# USB_A_USB_C.net
KiCad netlist of a schematic drawn in Altium Designer
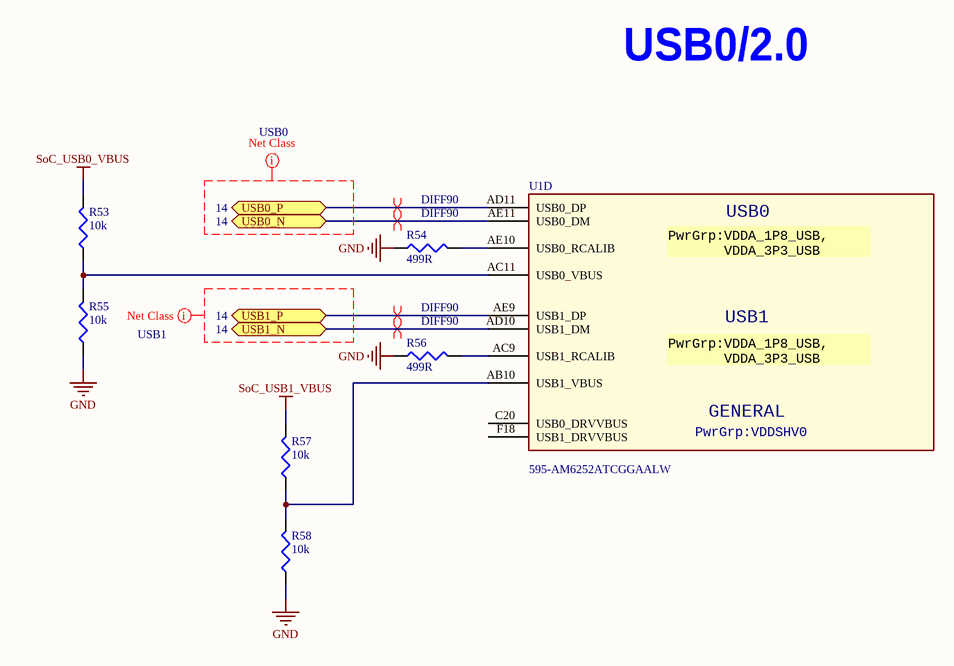
[diagram p0: USB_A & USB_C.SchDoc]

(export (version "E")
  (design (tool "Eeschema 10.0.6"))
  (components
    (comp (ref "R53")
      (value "10k")
      (footprint "R0402")
      (description "RES 10.0K OHM 1/16W 1% 0402 SMD")
      (fields
        (field (name "MANUFACTURER") "Yageo")
        (field (name "MANUFACTURER PART NUMBER") "RC0402FR-0710KL")
      )
      (libsource (lib "Schlib AM625") (part "RC0402FR-0710KL"))
    )
    (comp (ref "R54")
      (value "499R")
      (footprint "R0402")
      (description "RES SMD 499 OHM 0.1% 1/16W 0402")
      (fields
        (field (name "MANUFACTURER") "Yageo")
        (field (name "MANUFACTURER PART NUMBER") "RT0402BRD07499RL")
      )
      (libsource (lib "Schlib AM625") (part "RT0402BRD07499RL"))
    )
    (comp (ref "R55")
      (value "10k")
      (footprint "R0402")
      (description "RES 10.0K OHM 1/16W 1% 0402 SMD")
      (fields
        (field (name "MANUFACTURER") "Yageo")
        (field (name "MANUFACTURER PART NUMBER") "RC0402FR-0710KL")
      )
      (libsource (lib "Schlib AM625") (part "RC0402FR-0710KL"))
    )
    (comp (ref "R56")
      (value "499R")
      (footprint "R0402")
      (description "RES SMD 499 OHM 0.1% 1/16W 0402")
      (fields
        (field (name "MANUFACTURER") "Yageo")
        (field (name "MANUFACTURER PART NUMBER") "RT0402BRD07499RL")
      )
      (libsource (lib "Schlib AM625") (part "RT0402BRD07499RL"))
    )
    (comp (ref "R57")
      (value "10k")
      (footprint "R0402")
      (description "RES 10.0K OHM 1/16W 1% 0402 SMD")
      (fields
        (field (name "MANUFACTURER") "Yageo")
        (field (name "MANUFACTURER PART NUMBER") "RC0402FR-0710KL")
      )
      (libsource (lib "Schlib AM625") (part "RC0402FR-0710KL"))
    )
    (comp (ref "R58")
      (value "10k")
      (footprint "R0402")
      (description "RES 10.0K OHM 1/16W 1% 0402 SMD")
      (fields
        (field (name "MANUFACTURER") "Yageo")
        (field (name "MANUFACTURER PART NUMBER") "RC0402FR-0710KL")
      )
      (libsource (lib "Schlib AM625") (part "RC0402FR-0710KL"))
    )
    (comp (ref "U1")
      (value "AM62-EVM_BGA425")
      (footprint "BGA425C50P25X25_1300X1300X89")
      (description "ARM® Cortex®-A53 Microprocessor IC Sitara™ 2 Core, 64-Bit 1.4GHz 425-FCCSP (13x13)")
      (fields
        (field (name "MANUFACTURER") "Texas Instruments")
        (field (name "MANUFACTURER PART NUMBER") "AM6252ATCGGAALW")
        (field (name "SUPPLIER PART NUMBER 1") "595-AM6252ATCGGAALW")
      )
      (libsource (lib "Schlib AM625") (part "AM62-EVM_BGA425"))
    )
  )
  (nets
    (net (code "1") (name "/USB0_N") (class "Default")
      (node (ref "U1") (pin "AE11") (pinfunction "USB0_DM_AE11") (pintype "passive"))
    )
    (net (code "2") (name "/USB0_P") (class "Default")
      (node (ref "U1") (pin "AD11") (pinfunction "USB0_DP_AD11") (pintype "passive"))
    )
    (net (code "3") (name "/USB1_N") (class "Default")
      (node (ref "U1") (pin "AD10") (pinfunction "USB1_DM_AD10") (pintype "passive"))
    )
    (net (code "4") (name "/USB1_P") (class "Default")
      (node (ref "U1") (pin "AE9") (pinfunction "USB1_DP_AE9") (pintype "passive"))
    )
    (net (code "5") (name "GND") (class "Default")
      (node (ref "R54") (pin "1") (pinfunction "1_1") (pintype "passive"))
      (node (ref "R55") (pin "1") (pinfunction "1_1") (pintype "passive"))
      (node (ref "R56") (pin "1") (pinfunction "1_1") (pintype "passive"))
      (node (ref "R58") (pin "1") (pinfunction "1_1") (pintype "passive"))
    )
    (net (code "6") (name "Net-(U1D-USB0_RCALIB)") (class "Default")
      (node (ref "R54") (pin "2") (pinfunction "2_2") (pintype "passive"))
      (node (ref "U1") (pin "AE10") (pinfunction "USB0_RCALIB_AE10") (pintype "passive"))
    )
    (net (code "7") (name "Net-(U1D-USB0_VBUS)") (class "Default")
      (node (ref "R53") (pin "1") (pinfunction "1_1") (pintype "passive"))
      (node (ref "R55") (pin "2") (pinfunction "2_2") (pintype "passive"))
      (node (ref "U1") (pin "AC11") (pinfunction "USB0_VBUS_AC11") (pintype "passive"))
    )
    (net (code "8") (name "Net-(U1D-USB1_RCALIB)") (class "Default")
      (node (ref "R56") (pin "2") (pinfunction "2_2") (pintype "passive"))
      (node (ref "U1") (pin "AC9") (pinfunction "USB1_RCALIB_AC9") (pintype "passive"))
    )
    (net (code "9") (name "Net-(U1D-USB1_VBUS)") (class "Default")
      (node (ref "R57") (pin "1") (pinfunction "1_1") (pintype "passive"))
      (node (ref "R58") (pin "2") (pinfunction "2_2") (pintype "passive"))
      (node (ref "U1") (pin "AB10") (pinfunction "USB1_VBUS_AB10") (pintype "passive"))
    )
    (net (code "10") (name "SoC_USB0_VBUS") (class "Default")
      (node (ref "R53") (pin "2") (pinfunction "2_2") (pintype "passive"))
    )
    (net (code "11") (name "SoC_USB1_VBUS") (class "Default")
      (node (ref "R57") (pin "2") (pinfunction "2_2") (pintype "passive"))
    )
    (net (code "12") (name "unconnected-(U1D-USB0_DRVVBUS-PadC20)") (class "Default")
      (node (ref "U1") (pin "C20") (pinfunction "USB0_DRVVBUS_C20") (pintype "passive"))
    )
    (net (code "13") (name "unconnected-(U1D-USB1_DRVVBUS-PadF18)") (class "Default")
      (node (ref "U1") (pin "F18") (pinfunction "USB1_DRVVBUS_F18") (pintype "passive"))
    )
  )
)
